# ausbee_carte_alim.net
KiCad netlist of a schematic drawn in EAGLE
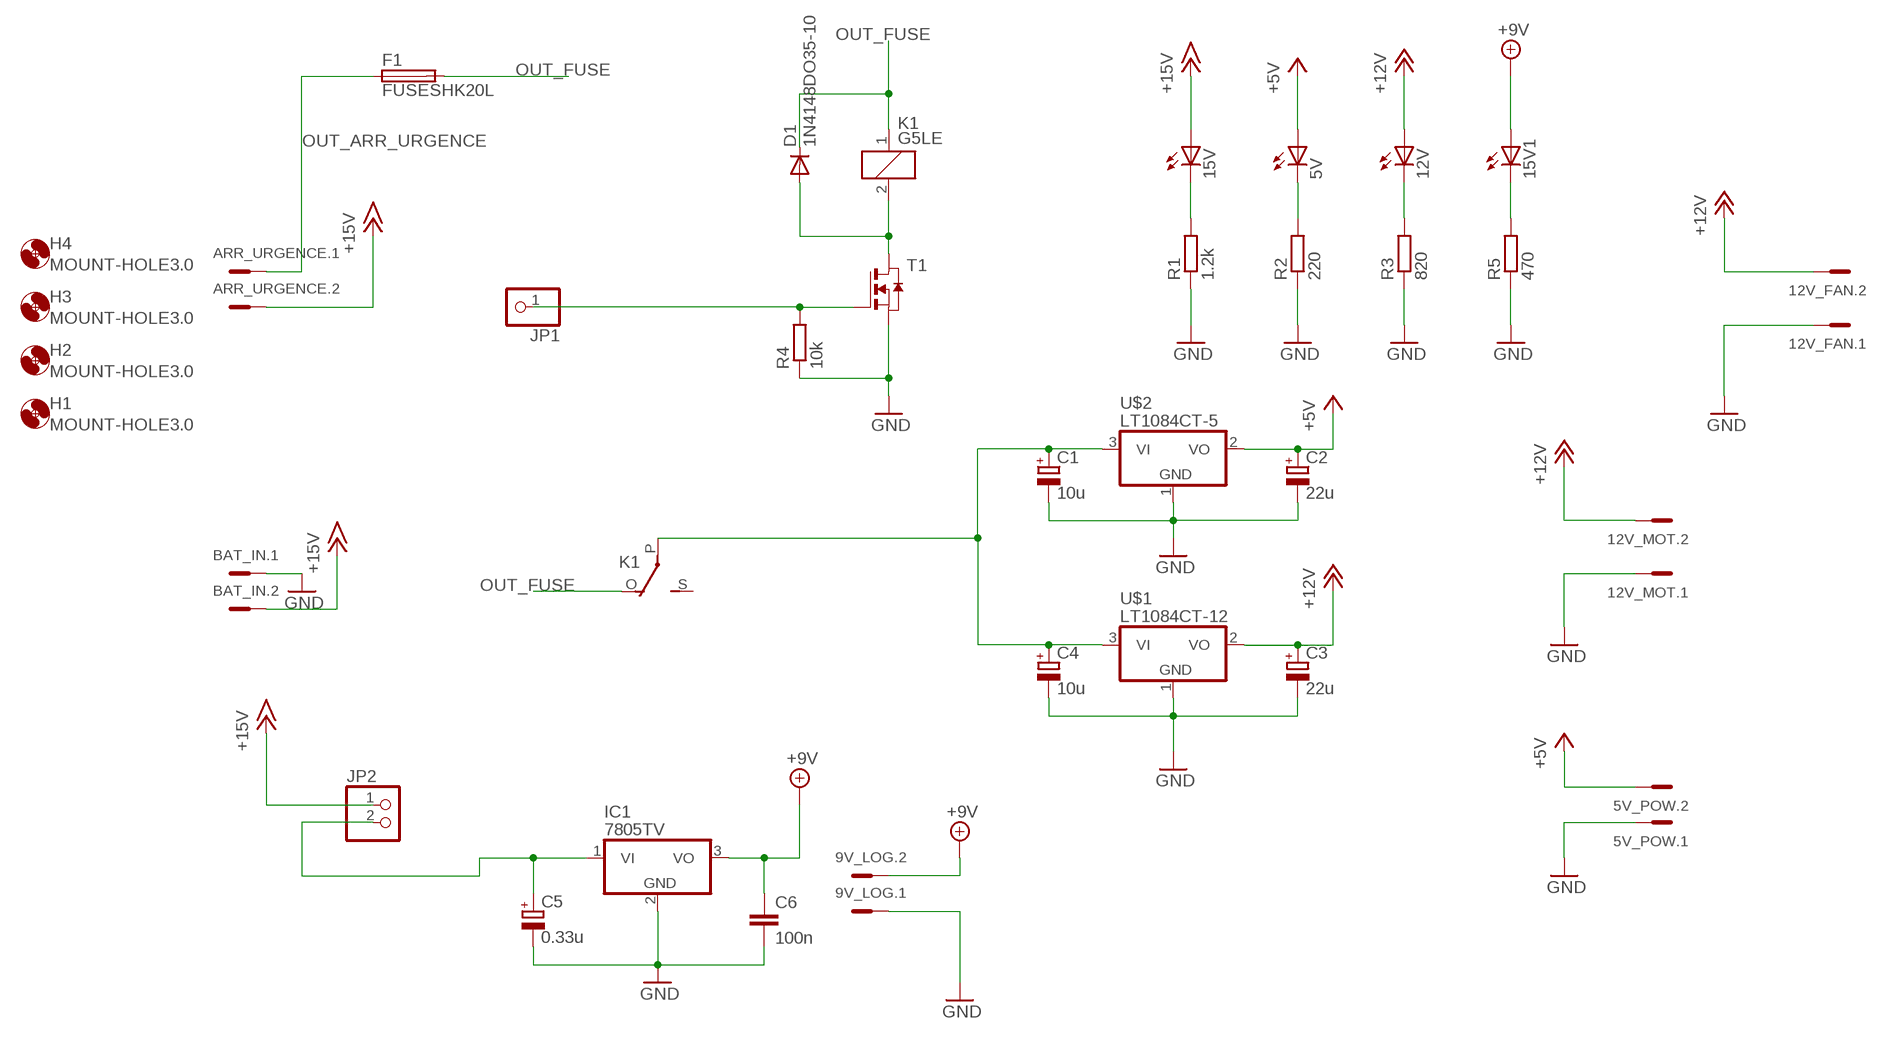
[diagram p0: schematic, sheet 1]

(export (version "E")
  (design (tool "Eeschema 10.0.6"))
  (components
    (comp (ref "5V")
      (value "LED3MM")
      (footprint "eagle-import:LED3MM")
      (libsource (lib "eagle-import") (part "LED3MM"))
    )
    (comp (ref "5V_POW")
      (value "MCV2")
      (footprint "eagle-import:MCV2")
      (libsource (lib "eagle-import") (part "MCV2"))
    )
    (comp (ref "9V_LOG")
      (value "MCV2")
      (footprint "eagle-import:MCV2")
      (libsource (lib "eagle-import") (part "MCV2"))
    )
    (comp (ref "12V")
      (value "LED3MM")
      (footprint "eagle-import:LED3MM")
      (libsource (lib "eagle-import") (part "LED3MM"))
    )
    (comp (ref "12V_FAN")
      (value "MCV2")
      (footprint "eagle-import:MCV2")
      (libsource (lib "eagle-import") (part "MCV2"))
    )
    (comp (ref "12V_MOT")
      (value "MCV2")
      (footprint "eagle-import:MCV2")
      (libsource (lib "eagle-import") (part "MCV2"))
    )
    (comp (ref "15V")
      (value "LED3MM")
      (footprint "eagle-import:LED3MM")
      (libsource (lib "eagle-import") (part "LED3MM"))
    )
    (comp (ref "15V1")
      (value "LED3MM")
      (footprint "eagle-import:LED3MM")
      (libsource (lib "eagle-import") (part "LED3MM"))
    )
    (comp (ref "ARR_URGENCE")
      (value "MCV2")
      (footprint "eagle-import:MCV2")
      (libsource (lib "eagle-import") (part "MCV2"))
    )
    (comp (ref "BAT_IN")
      (value "MCV2")
      (footprint "eagle-import:MCV2")
      (libsource (lib "eagle-import") (part "MCV2"))
    )
    (comp (ref "C1")
      (value "10u")
      (footprint "eagle-import:E5-8,5")
      (libsource (lib "eagle-import") (part "CPOL-EUE5-8.5"))
    )
    (comp (ref "C2")
      (value "22u")
      (footprint "eagle-import:CT7343")
      (libsource (lib "eagle-import") (part "CPOL-EUCT7343"))
    )
    (comp (ref "C3")
      (value "22u")
      (footprint "eagle-import:CT7343")
      (libsource (lib "eagle-import") (part "CPOL-EUCT7343"))
    )
    (comp (ref "C4")
      (value "10u")
      (footprint "eagle-import:E5-8,5")
      (libsource (lib "eagle-import") (part "CPOL-EUE5-8.5"))
    )
    (comp (ref "C5")
      (value "0.33u")
      (footprint "eagle-import:E2,5-5")
      (libsource (lib "eagle-import") (part "CPOL-EUE2.5-5"))
    )
    (comp (ref "C6")
      (value "100n")
      (footprint "eagle-import:C0805")
      (libsource (lib "eagle-import") (part "C-EUC0805"))
    )
    (comp (ref "D1")
      (value "1N4148DO35-10")
      (footprint "eagle-import:DO35-10")
      (libsource (lib "eagle-import") (part "1N4148DO35-10"))
    )
    (comp (ref "F1")
      (value "FUSESHK20L")
      (footprint "eagle-import:SHK20L")
      (libsource (lib "eagle-import") (part "FUSESHK20L"))
    )
    (comp (ref "H1")
      (value "MOUNT-HOLE3.0")
      (footprint "eagle-import:3,0")
      (libsource (lib "eagle-import") (part "MOUNT-HOLE3.0"))
    )
    (comp (ref "H2")
      (value "MOUNT-HOLE3.0")
      (footprint "eagle-import:3,0")
      (libsource (lib "eagle-import") (part "MOUNT-HOLE3.0"))
    )
    (comp (ref "H3")
      (value "MOUNT-HOLE3.0")
      (footprint "eagle-import:3,0")
      (libsource (lib "eagle-import") (part "MOUNT-HOLE3.0"))
    )
    (comp (ref "H4")
      (value "MOUNT-HOLE3.0")
      (footprint "eagle-import:3,0")
      (libsource (lib "eagle-import") (part "MOUNT-HOLE3.0"))
    )
    (comp (ref "IC1")
      (value "7805TV")
      (footprint "eagle-import:TO220V")
      (libsource (lib "eagle-import") (part "78TV05"))
    )
    (comp (ref "JP1")
      (value "PINHD-1X1")
      (footprint "eagle-import:1X01")
      (libsource (lib "eagle-import") (part "PINHD-1X1"))
    )
    (comp (ref "JP2")
      (value "PINHD-1X2")
      (footprint "eagle-import:1X02")
      (libsource (lib "eagle-import") (part "PINHD-1X2"))
    )
    (comp (ref "K1")
      (value "G5LE")
      (footprint "eagle-import:G5LE")
      (libsource (lib "eagle-import") (part "G5LE"))
    )
    (comp (ref "R1")
      (value "1.2k")
      (footprint "eagle-import:0309V")
      (libsource (lib "eagle-import") (part "R-EU_0309/V"))
    )
    (comp (ref "R2")
      (value "220")
      (footprint "eagle-import:0309V")
      (libsource (lib "eagle-import") (part "R-EU_0309/V"))
    )
    (comp (ref "R3")
      (value "820")
      (footprint "eagle-import:0309V")
      (libsource (lib "eagle-import") (part "R-EU_0309/V"))
    )
    (comp (ref "R4")
      (value "10k")
      (footprint "eagle-import:0309V")
      (libsource (lib "eagle-import") (part "R-EU_0309/V"))
    )
    (comp (ref "R5")
      (value "470")
      (footprint "eagle-import:0309V")
      (libsource (lib "eagle-import") (part "R-EU_0309/V"))
    )
    (comp (ref "T1")
      (value "NMOSSOT23")
      (footprint "eagle-import:SOT-23")
      (libsource (lib "eagle-import") (part "NMOSSOT23"))
    )
    (comp (ref "U$1")
      (value "LT1084CT-12")
      (footprint "eagle-import:TO220V")
      (libsource (lib "eagle-import") (part "LT1084CT-12"))
    )
    (comp (ref "U$2")
      (value "LT1084CT-5")
      (footprint "eagle-import:TO220V")
      (libsource (lib "eagle-import") (part "LT1084CT-5"))
    )
  )
  (nets
    (net (code "1") (name "+5V") (class "Default")
      (node (ref "5V") (pin "A") (pinfunction "A_A") (pintype "passive"))
      (node (ref "5V_POW") (pin "2") (pinfunction "SK_2") (pintype "passive"))
      (node (ref "C2") (pin "+") (pinfunction "+_+") (pintype "passive"))
      (node (ref "U$2") (pin "2") (pinfunction "VO_2") (pintype "passive"))
    )
    (net (code "2") (name "+9V") (class "Default")
      (node (ref "15V1") (pin "A") (pinfunction "A_A") (pintype "passive"))
      (node (ref "9V_LOG") (pin "2") (pinfunction "SK_2") (pintype "passive"))
      (node (ref "C6") (pin "1") (pinfunction "1_1") (pintype "passive"))
      (node (ref "IC1") (pin "3") (pinfunction "VO_3") (pintype "passive"))
    )
    (net (code "3") (name "+12V") (class "Default")
      (node (ref "12V") (pin "A") (pinfunction "A_A") (pintype "passive"))
      (node (ref "12V_FAN") (pin "2") (pinfunction "SK_2") (pintype "passive"))
      (node (ref "12V_MOT") (pin "2") (pinfunction "SK_2") (pintype "passive"))
      (node (ref "C3") (pin "+") (pinfunction "+_+") (pintype "passive"))
      (node (ref "U$1") (pin "2") (pinfunction "VO_2") (pintype "passive"))
    )
    (net (code "4") (name "+15V") (class "Default")
      (node (ref "15V") (pin "A") (pinfunction "A_A") (pintype "passive"))
      (node (ref "ARR_URGENCE") (pin "2") (pinfunction "SK_2") (pintype "passive"))
      (node (ref "BAT_IN") (pin "2") (pinfunction "SK_2") (pintype "passive"))
      (node (ref "JP2") (pin "1") (pinfunction "1_1") (pintype "passive"))
    )
    (net (code "5") (name "/OUT_ARR_URGENCE") (class "Default")
      (node (ref "ARR_URGENCE") (pin "1") (pinfunction "SK_1") (pintype "passive"))
      (node (ref "F1") (pin "1A") (pinfunction "1_1A") (pintype "passive"))
    )
    (net (code "6") (name "/OUT_FUSE") (class "Default")
      (node (ref "D1") (pin "C") (pinfunction "C_C") (pintype "passive"))
      (node (ref "F1") (pin "2A") (pinfunction "2_2A") (pintype "passive"))
      (node (ref "K1") (pin "1") (pinfunction "1_1") (pintype "passive"))
      (node (ref "K1") (pin "O") (pinfunction "O_O") (pintype "passive"))
    )
    (net (code "7") (name "GND") (class "Default")
      (node (ref "12V_FAN") (pin "1") (pinfunction "SK_1") (pintype "passive"))
      (node (ref "12V_MOT") (pin "1") (pinfunction "SK_1") (pintype "passive"))
      (node (ref "5V_POW") (pin "1") (pinfunction "SK_1") (pintype "passive"))
      (node (ref "9V_LOG") (pin "1") (pinfunction "SK_1") (pintype "passive"))
      (node (ref "BAT_IN") (pin "1") (pinfunction "SK_1") (pintype "passive"))
      (node (ref "C1") (pin "-") (pinfunction "-_-") (pintype "passive"))
      (node (ref "C2") (pin "-") (pinfunction "-_-") (pintype "passive"))
      (node (ref "C3") (pin "-") (pinfunction "-_-") (pintype "passive"))
      (node (ref "C4") (pin "-") (pinfunction "-_-") (pintype "passive"))
      (node (ref "C5") (pin "-") (pinfunction "-_-") (pintype "passive"))
      (node (ref "C6") (pin "2") (pinfunction "2_2") (pintype "passive"))
      (node (ref "IC1") (pin "2") (pinfunction "GND_2") (pintype "passive"))
      (node (ref "R1") (pin "1") (pinfunction "1_1") (pintype "passive"))
      (node (ref "R2") (pin "1") (pinfunction "1_1") (pintype "passive"))
      (node (ref "R3") (pin "1") (pinfunction "1_1") (pintype "passive"))
      (node (ref "R4") (pin "1") (pinfunction "1_1") (pintype "passive"))
      (node (ref "R5") (pin "1") (pinfunction "1_1") (pintype "passive"))
      (node (ref "T1") (pin "2") (pinfunction "S_2") (pintype "passive"))
      (node (ref "U$1") (pin "1") (pinfunction "GND_1") (pintype "passive"))
      (node (ref "U$2") (pin "1") (pinfunction "GND_1") (pintype "passive"))
    )
    (net (code "8") (name "Net-(5V-C)") (class "Default")
      (node (ref "5V") (pin "K") (pinfunction "C_K") (pintype "passive"))
      (node (ref "R2") (pin "2") (pinfunction "2_2") (pintype "passive"))
    )
    (net (code "9") (name "Net-(12V-C)") (class "Default")
      (node (ref "12V") (pin "K") (pinfunction "C_K") (pintype "passive"))
      (node (ref "R3") (pin "2") (pinfunction "2_2") (pintype "passive"))
    )
    (net (code "10") (name "Net-(15V-C)") (class "Default")
      (node (ref "15V") (pin "K") (pinfunction "C_K") (pintype "passive"))
      (node (ref "R1") (pin "2") (pinfunction "2_2") (pintype "passive"))
    )
    (net (code "11") (name "Net-(15V1-C)") (class "Default")
      (node (ref "15V1") (pin "K") (pinfunction "C_K") (pintype "passive"))
      (node (ref "R5") (pin "2") (pinfunction "2_2") (pintype "passive"))
    )
    (net (code "12") (name "Net-(IC1-VI)") (class "Default")
      (node (ref "C5") (pin "+") (pinfunction "+_+") (pintype "passive"))
      (node (ref "IC1") (pin "1") (pinfunction "VI_1") (pintype "input"))
      (node (ref "JP2") (pin "2") (pinfunction "2_2") (pintype "passive"))
    )
    (net (code "13") (name "Net-(T1-D)") (class "Default")
      (node (ref "D1") (pin "A") (pinfunction "A_A") (pintype "passive"))
      (node (ref "K1") (pin "2") (pinfunction "2_2") (pintype "passive"))
      (node (ref "T1") (pin "1") (pinfunction "D_1") (pintype "passive"))
    )
    (net (code "14") (name "Net-(T1-G)") (class "Default")
      (node (ref "JP1") (pin "1") (pinfunction "1_1") (pintype "passive"))
      (node (ref "R4") (pin "2") (pinfunction "2_2") (pintype "passive"))
      (node (ref "T1") (pin "3") (pinfunction "G_3") (pintype "passive"))
    )
    (net (code "15") (name "Net-(U$1-VI)") (class "Default")
      (node (ref "C1") (pin "+") (pinfunction "+_+") (pintype "passive"))
      (node (ref "C4") (pin "+") (pinfunction "+_+") (pintype "passive"))
      (node (ref "K1") (pin "P") (pinfunction "P_P") (pintype "passive"))
      (node (ref "U$1") (pin "3") (pinfunction "VI_3") (pintype "input"))
      (node (ref "U$2") (pin "3") (pinfunction "VI_3") (pintype "input"))
    )
    (net (code "16") (name "unconnected-(K1-PadS)") (class "Default")
      (node (ref "K1") (pin "S") (pinfunction "S_S") (pintype "passive"))
    )
  )
)
